# clapper_6.net
KiCad netlist of a schematic drawn in EAGLE
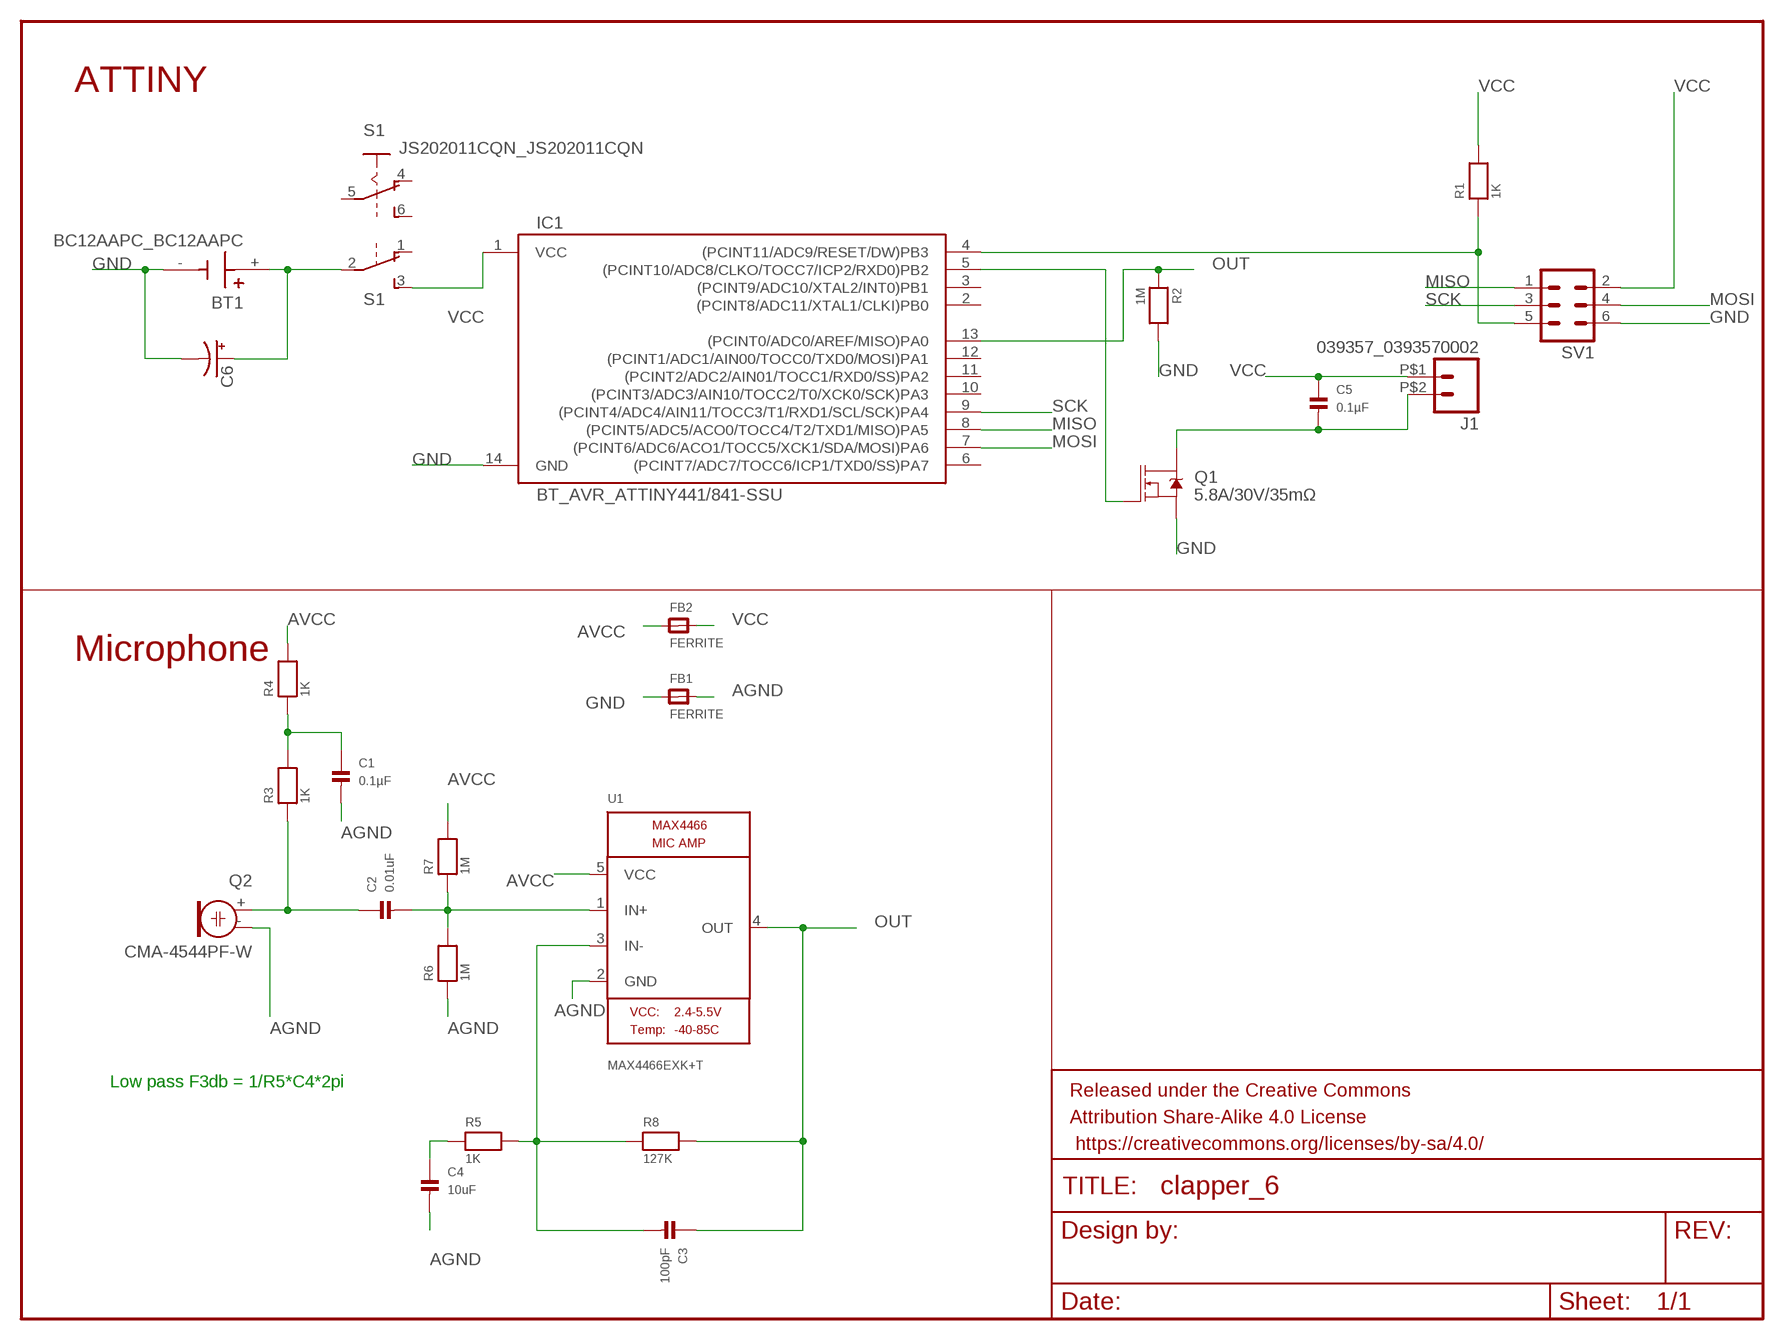
[diagram p0: schematic, sheet 1]

(export (version "E")
  (design (tool "Eeschema 10.0.6"))
  (components
    (comp (ref "BT1")
      (value "BC12AAPC_BC12AAPC")
      (footprint "eagle-import:BC12AAPC_BAT_BC12AAPC")
      (fields (field (name "MF") "MPD _Memory") (field (name "MP") "BC12AAPC"))
      (libsource (lib "eagle-import") (part "BC12AAPC_BC12AAPC"))
    )
    (comp (ref "C1")
      (value "0.1µF")
      (footprint "eagle-import:MICROBUILDER_0805")
      (libsource (lib "eagle-import") (part "MICROBUILDER_CAP_CERAMIC0805"))
    )
    (comp (ref "C2")
      (value "0.01uF")
      (footprint "eagle-import:MICROBUILDER_0805")
      (libsource (lib "eagle-import") (part "MICROBUILDER_CAP_CERAMIC0805"))
    )
    (comp (ref "C3")
      (value "100pF")
      (footprint "eagle-import:MICROBUILDER_0805")
      (libsource (lib "eagle-import") (part "MICROBUILDER_CAP_CERAMIC0805"))
    )
    (comp (ref "C4")
      (value "10uF")
      (footprint "eagle-import:MICROBUILDER_0805")
      (libsource (lib "eagle-import") (part "MICROBUILDER_CAP_CERAMIC0805"))
    )
    (comp (ref "C5")
      (value "0.1µF")
      (footprint "eagle-import:MICROBUILDER_0805")
      (libsource (lib "eagle-import") (part "MICROBUILDER_CAP_CERAMIC0805"))
    )
    (comp (ref "C6")
      (value "CPOL-USE2.5-6")
      (footprint "eagle-import:E2,5-6")
      (libsource (lib "eagle-import") (part "CPOL-USE2.5-6"))
    )
    (comp (ref "FB1")
      (value "FERRITE")
      (footprint "eagle-import:MICROBUILDER_0805")
      (libsource (lib "eagle-import") (part "MICROBUILDER_FERRITE0805"))
    )
    (comp (ref "FB2")
      (value "FERRITE")
      (footprint "eagle-import:MICROBUILDER_0805")
      (libsource (lib "eagle-import") (part "MICROBUILDER_FERRITE0805"))
    )
    (comp (ref "FRAME2")
      (value "FRAME-LETTER")
      (footprint "eagle-import:CREATIVE_COMMONS")
      (libsource (lib "eagle-import") (part "FRAME-LETTER"))
    )
    (comp (ref "IC1")
      (value "BT_AVR_ATTINY441/841-SSU")
      (footprint "eagle-import:BT_AVR_SOIC14N")
      (libsource (lib "eagle-import") (part "BT_AVR_ATTINY441/841-SSU"))
    )
    (comp (ref "J1")
      (value "039357_0393570002")
      (footprint "eagle-import:039357_0393570002")
      (libsource (lib "eagle-import") (part "039357_0393570002"))
    )
    (comp (ref "Q1")
      (value "5.8A/30V/35mΩ")
      (footprint "eagle-import:SOT23-3")
      (libsource (lib "eagle-import") (part "MOSFET-NCH-AO3404A"))
    )
    (comp (ref "Q2")
      (value "CMA-4544PF-W")
      (footprint "eagle-import:MICROBUILDER_ELECTRET_9.7")
      (libsource (lib "eagle-import") (part "MICROBUILDER_ELECTRET"))
    )
    (comp (ref "R1")
      (value "1K")
      (footprint "eagle-import:MICROBUILDER_0805")
      (libsource (lib "eagle-import") (part "MICROBUILDER_RESISTOR0805"))
    )
    (comp (ref "R2")
      (value "1M")
      (footprint "eagle-import:MICROBUILDER_0805")
      (libsource (lib "eagle-import") (part "MICROBUILDER_RESISTOR0805"))
    )
    (comp (ref "R3")
      (value "1K")
      (footprint "eagle-import:MICROBUILDER_0805")
      (libsource (lib "eagle-import") (part "MICROBUILDER_RESISTOR0805"))
    )
    (comp (ref "R4")
      (value "1K")
      (footprint "eagle-import:MICROBUILDER_0805")
      (libsource (lib "eagle-import") (part "MICROBUILDER_RESISTOR0805"))
    )
    (comp (ref "R5")
      (value "1K")
      (footprint "eagle-import:MICROBUILDER_0805")
      (libsource (lib "eagle-import") (part "MICROBUILDER_RESISTOR0805"))
    )
    (comp (ref "R6")
      (value "1M")
      (footprint "eagle-import:MICROBUILDER_0805")
      (libsource (lib "eagle-import") (part "MICROBUILDER_RESISTOR0805"))
    )
    (comp (ref "R7")
      (value "1M")
      (footprint "eagle-import:MICROBUILDER_0805")
      (libsource (lib "eagle-import") (part "MICROBUILDER_RESISTOR0805"))
    )
    (comp (ref "R8")
      (value "127K")
      (footprint "eagle-import:MICROBUILDER_0805")
      (libsource (lib "eagle-import") (part "MICROBUILDER_RESISTOR0805"))
    )
    (comp (ref "S1")
      (value "JS202011CQN_JS202011CQN")
      (footprint "eagle-import:JS202011CQN_JS202011CQN")
      (fields (field (name "MF") "CK") (field (name "MP") "JS202011CQN"))
      (libsource (lib "eagle-import") (part "JS202011CQN_JS202011CQN"))
    )
    (comp (ref "SV1")
      (value "CWT_MA03-2")
      (footprint "eagle-import:CWT_MA03-2")
      (libsource (lib "eagle-import") (part "CWT_MA03-2"))
    )
    (comp (ref "U1")
      (value "MAX4466EXK+T")
      (footprint "eagle-import:MICROBUILDER_SC70-5")
      (libsource (lib "eagle-import") (part "MICROBUILDER_MAX4466{dblquote}{dblquote}"))
    )
  )
  (nets
    (net (code "1") (name "/AGND") (class "Default")
      (node (ref "C1") (pin "2") (pinfunction "P$2_2") (pintype "passive"))
      (node (ref "C4") (pin "2") (pinfunction "P$2_2") (pintype "passive"))
      (node (ref "FB1") (pin "2") (pinfunction "P$2_2") (pintype "passive"))
      (node (ref "Q2") (pin "-") (pinfunction "1_-") (pintype "passive"))
      (node (ref "R6") (pin "1") (pinfunction "1_1") (pintype "passive"))
      (node (ref "U1") (pin "2") (pinfunction "GND_2") (pintype "bidirectional"))
    )
    (net (code "2") (name "/AVCC") (class "Default")
      (node (ref "FB2") (pin "1") (pinfunction "P$1_1") (pintype "passive"))
      (node (ref "R4") (pin "2") (pinfunction "2_2") (pintype "passive"))
      (node (ref "R7") (pin "2") (pinfunction "2_2") (pintype "passive"))
      (node (ref "U1") (pin "5") (pinfunction "VCC_5") (pintype "bidirectional"))
    )
    (net (code "3") (name "/GND") (class "Default")
      (node (ref "BT1") (pin "-") (pinfunction "-_-") (pintype "passive"))
      (node (ref "C6") (pin "-") (pinfunction "-_-") (pintype "passive"))
      (node (ref "FB1") (pin "1") (pinfunction "P$1_1") (pintype "passive"))
      (node (ref "IC1") (pin "14") (pinfunction "GND_14") (pintype "bidirectional"))
      (node (ref "Q1") (pin "2") (pinfunction "S_2") (pintype "bidirectional"))
      (node (ref "R2") (pin "2") (pinfunction "2_2") (pintype "passive"))
      (node (ref "SV1") (pin "6") (pinfunction "6_6") (pintype "passive"))
    )
    (net (code "4") (name "/MISO") (class "Default")
      (node (ref "IC1") (pin "8") (pinfunction "(PCINT5/ADC5/ACO0/TOCC4/T2/TXD1/MISO)PA5_8") (pintype "bidirectional"))
      (node (ref "SV1") (pin "1") (pinfunction "1_1") (pintype "passive"))
    )
    (net (code "5") (name "/MOSI") (class "Default")
      (node (ref "IC1") (pin "7") (pinfunction "(PCINT6/ADC6/ACO1/TOCC5/XCK1/SDA/MOSI)PA6_7") (pintype "bidirectional"))
      (node (ref "SV1") (pin "4") (pinfunction "4_4") (pintype "passive"))
    )
    (net (code "6") (name "/OUT") (class "Default")
      (node (ref "C3") (pin "1") (pinfunction "P$1_1") (pintype "passive"))
      (node (ref "IC1") (pin "13") (pinfunction "(PCINT0/ADC0/AREF/MISO)PA0_13") (pintype "bidirectional"))
      (node (ref "R2") (pin "1") (pinfunction "1_1") (pintype "passive"))
      (node (ref "R8") (pin "2") (pinfunction "2_2") (pintype "passive"))
      (node (ref "U1") (pin "4") (pinfunction "OUT_4") (pintype "bidirectional"))
    )
    (net (code "7") (name "/SCK") (class "Default")
      (node (ref "IC1") (pin "9") (pinfunction "(PCINT4/ADC4/AIN11/TOCC3/T1/RXD1/SCL/SCK)PA4_9") (pintype "bidirectional"))
      (node (ref "SV1") (pin "3") (pinfunction "3_3") (pintype "passive"))
    )
    (net (code "8") (name "/VCC") (class "Default")
      (node (ref "C5") (pin "1") (pinfunction "P$1_1") (pintype "passive"))
      (node (ref "FB2") (pin "2") (pinfunction "P$2_2") (pintype "passive"))
      (node (ref "IC1") (pin "1") (pinfunction "VCC_1") (pintype "bidirectional"))
      (node (ref "J1") (pin "P$1") (pinfunction "1_P$1") (pintype "passive"))
      (node (ref "R1") (pin "2") (pinfunction "2_2") (pintype "passive"))
      (node (ref "S1") (pin "3") (pinfunction "S_3") (pintype "passive"))
      (node (ref "SV1") (pin "2") (pinfunction "2_2") (pintype "passive"))
    )
    (net (code "9") (name "Net-(C1-P$1)") (class "Default")
      (node (ref "C1") (pin "1") (pinfunction "P$1_1") (pintype "passive"))
      (node (ref "R3") (pin "2") (pinfunction "2_2") (pintype "passive"))
      (node (ref "R4") (pin "1") (pinfunction "1_1") (pintype "passive"))
    )
    (net (code "10") (name "Net-(C2-P$1)") (class "Default")
      (node (ref "C2") (pin "1") (pinfunction "P$1_1") (pintype "passive"))
      (node (ref "Q2") (pin "+") (pinfunction "2_+") (pintype "passive"))
      (node (ref "R3") (pin "1") (pinfunction "1_1") (pintype "passive"))
    )
    (net (code "11") (name "Net-(C2-P$2)") (class "Default")
      (node (ref "C2") (pin "2") (pinfunction "P$2_2") (pintype "passive"))
      (node (ref "R6") (pin "2") (pinfunction "2_2") (pintype "passive"))
      (node (ref "R7") (pin "1") (pinfunction "1_1") (pintype "passive"))
      (node (ref "U1") (pin "1") (pinfunction "IN+_1") (pintype "bidirectional"))
    )
    (net (code "12") (name "Net-(C3-P$2)") (class "Default")
      (node (ref "C3") (pin "2") (pinfunction "P$2_2") (pintype "passive"))
      (node (ref "R5") (pin "2") (pinfunction "2_2") (pintype "passive"))
      (node (ref "R8") (pin "1") (pinfunction "1_1") (pintype "passive"))
      (node (ref "U1") (pin "3") (pinfunction "IN-_3") (pintype "bidirectional"))
    )
    (net (code "13") (name "Net-(C4-P$1)") (class "Default")
      (node (ref "C4") (pin "1") (pinfunction "P$1_1") (pintype "passive"))
      (node (ref "R5") (pin "1") (pinfunction "1_1") (pintype "passive"))
    )
    (net (code "14") (name "Net-(C5-P$2)") (class "Default")
      (node (ref "C5") (pin "2") (pinfunction "P$2_2") (pintype "passive"))
      (node (ref "J1") (pin "P$2") (pinfunction "2_P$2") (pintype "passive"))
      (node (ref "Q1") (pin "3") (pinfunction "D_3") (pintype "bidirectional"))
    )
    (net (code "15") (name "Net-(IC1-(PCINT10{slash}ADC8{slash}CLKO{slash}TOCC7{slash}ICP2{slash}RXD0)PB2)") (class "Default")
      (node (ref "IC1") (pin "5") (pinfunction "(PCINT10/ADC8/CLKO/TOCC7/ICP2/RXD0)PB2_5") (pintype "bidirectional"))
      (node (ref "Q1") (pin "1") (pinfunction "G_1") (pintype "bidirectional"))
    )
    (net (code "16") (name "Net-(IC1-(PCINT11{slash}ADC9{slash}RESET{slash}DW)PB3)") (class "Default")
      (node (ref "IC1") (pin "4") (pinfunction "(PCINT11/ADC9/RESET/DW)PB3_4") (pintype "bidirectional"))
      (node (ref "R1") (pin "1") (pinfunction "1_1") (pintype "passive"))
      (node (ref "SV1") (pin "5") (pinfunction "5_5") (pintype "passive"))
    )
    (net (code "17") (name "Net-(S1B-P)") (class "Default")
      (node (ref "BT1") (pin "+") (pinfunction "+_+") (pintype "passive"))
      (node (ref "C6") (pin "+") (pinfunction "+_+") (pintype "passive"))
      (node (ref "S1") (pin "2") (pinfunction "P_2") (pintype "passive"))
    )
    (net (code "18") (name "unconnected-(IC1-(PCINT1{slash}ADC1{slash}AIN00{slash}TOCC0{slash}TXD0{slash}MOSI)PA1-Pad12)") (class "Default")
      (node (ref "IC1") (pin "12") (pinfunction "(PCINT1/ADC1/AIN00/TOCC0/TXD0/MOSI)PA1_12") (pintype "bidirectional"))
    )
    (net (code "19") (name "unconnected-(IC1-(PCINT2{slash}ADC2{slash}AIN01{slash}TOCC1{slash}RXD0{slash}SS)PA2-Pad11)") (class "Default")
      (node (ref "IC1") (pin "11") (pinfunction "(PCINT2/ADC2/AIN01/TOCC1/RXD0/SS)PA2_11") (pintype "bidirectional"))
    )
    (net (code "20") (name "unconnected-(IC1-(PCINT3{slash}ADC3{slash}AIN10{slash}TOCC2{slash}T0{slash}XCK0{slash}SCK)PA3-Pad10)") (class "Default")
      (node (ref "IC1") (pin "10") (pinfunction "(PCINT3/ADC3/AIN10/TOCC2/T0/XCK0/SCK)PA3_10") (pintype "bidirectional"))
    )
    (net (code "21") (name "unconnected-(IC1-(PCINT7{slash}ADC7{slash}TOCC6{slash}ICP1{slash}TXD0{slash}SS)PA7-Pad6)") (class "Default")
      (node (ref "IC1") (pin "6") (pinfunction "(PCINT7/ADC7/TOCC6/ICP1/TXD0/SS)PA7_6") (pintype "bidirectional"))
    )
    (net (code "22") (name "unconnected-(IC1-(PCINT8{slash}ADC11{slash}XTAL1{slash}CLKI)PB0-Pad2)") (class "Default")
      (node (ref "IC1") (pin "2") (pinfunction "(PCINT8/ADC11/XTAL1/CLKI)PB0_2") (pintype "bidirectional"))
    )
    (net (code "23") (name "unconnected-(IC1-(PCINT9{slash}ADC10{slash}XTAL2{slash}INT0)PB1-Pad3)") (class "Default")
      (node (ref "IC1") (pin "3") (pinfunction "(PCINT9/ADC10/XTAL2/INT0)PB1_3") (pintype "bidirectional"))
    )
    (net (code "24") (name "unconnected-(S1A-O-Pad4)") (class "Default")
      (node (ref "S1") (pin "4") (pinfunction "O_4") (pintype "passive"))
    )
    (net (code "25") (name "unconnected-(S1A-P-Pad5)") (class "Default")
      (node (ref "S1") (pin "5") (pinfunction "P_5") (pintype "passive"))
    )
    (net (code "26") (name "unconnected-(S1A-S-Pad6)") (class "Default")
      (node (ref "S1") (pin "6") (pinfunction "S_6") (pintype "passive"))
    )
    (net (code "27") (name "unconnected-(S1B-O-Pad1)") (class "Default")
      (node (ref "S1") (pin "1") (pinfunction "O_1") (pintype "passive"))
    )
  )
)
